# MCU_board_ATmega328p_v2_4_SN.net
KiCad netlist of a schematic drawn in EAGLE
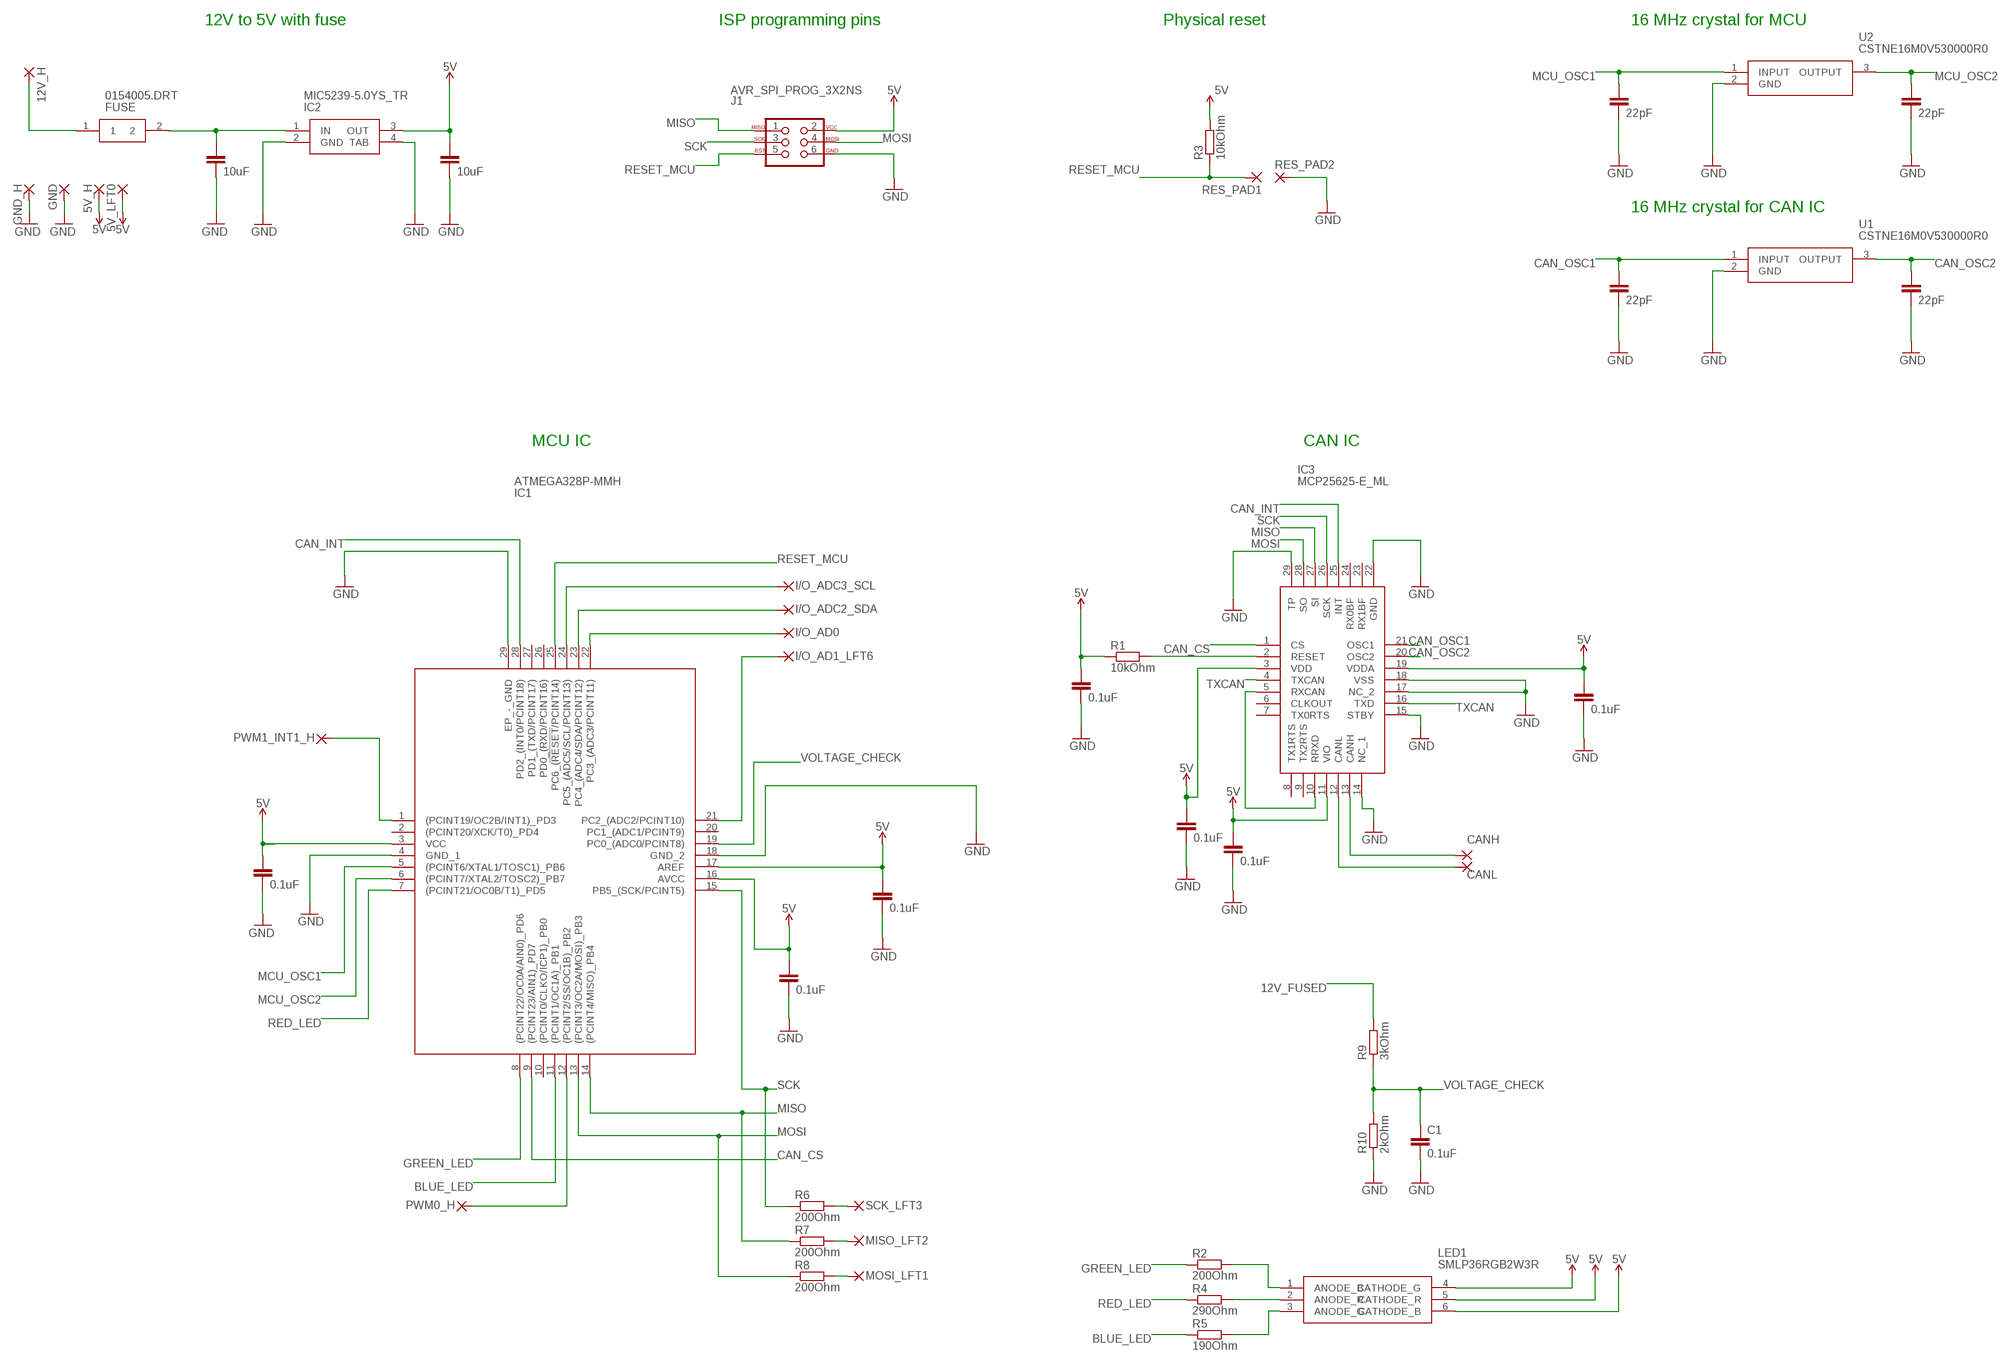
[diagram p0: schematic, sheet 1]

(export (version "E")
  (design (tool "Eeschema 10.0.6"))
  (components
    (comp (ref "5V")
      (value "5V_H")
      (footprint "eagle-import:2,15_1,0")
      (libsource (lib "eagle-import") (part "2,15/1,0"))
    )
    (comp (ref "5V1")
      (value "5V_LFT0")
      (footprint "eagle-import:2,15_1,0")
      (libsource (lib "eagle-import") (part "2,15/1,0"))
    )
    (comp (ref "12V_H")
      (value "12V")
      (footprint "eagle-import:2,15_1,0")
      (libsource (lib "eagle-import") (part "2,15/1,0"))
    )
    (comp (ref "C1")
      (value "0.1uF")
      (footprint "eagle-import:C0603")
      (libsource (lib "eagle-import") (part "CC0603"))
    )
    (comp (ref "C2")
      (value "22pF")
      (footprint "eagle-import:C0603")
      (libsource (lib "eagle-import") (part "CC0603"))
    )
    (comp (ref "C3")
      (value "22pF")
      (footprint "eagle-import:C0603")
      (libsource (lib "eagle-import") (part "CC0603"))
    )
    (comp (ref "C5")
      (value "22pF")
      (footprint "eagle-import:C0603")
      (libsource (lib "eagle-import") (part "CC0603"))
    )
    (comp (ref "C6")
      (value "0.1uF")
      (footprint "eagle-import:C0603")
      (libsource (lib "eagle-import") (part "CC0603"))
    )
    (comp (ref "C7")
      (value "0.1uF")
      (footprint "eagle-import:C0603")
      (libsource (lib "eagle-import") (part "CC0603"))
    )
    (comp (ref "C8")
      (value "0.1uF")
      (footprint "eagle-import:C0603")
      (libsource (lib "eagle-import") (part "CC0603"))
    )
    (comp (ref "C9")
      (value "22pF")
      (footprint "eagle-import:C0603")
      (libsource (lib "eagle-import") (part "CC0603"))
    )
    (comp (ref "C10")
      (value "10uF")
      (footprint "eagle-import:C0603")
      (libsource (lib "eagle-import") (part "CC0603"))
    )
    (comp (ref "C11")
      (value "10uF")
      (footprint "eagle-import:C0603")
      (libsource (lib "eagle-import") (part "CC0603"))
    )
    (comp (ref "C12")
      (value "0.1uF")
      (footprint "eagle-import:C0603")
      (libsource (lib "eagle-import") (part "CC0603"))
    )
    (comp (ref "C13")
      (value "0.1uF")
      (footprint "eagle-import:C0603")
      (libsource (lib "eagle-import") (part "CC0603"))
    )
    (comp (ref "C16")
      (value "0.1uF")
      (footprint "eagle-import:C0603")
      (libsource (lib "eagle-import") (part "CC0603"))
    )
    (comp (ref "C17")
      (value "0.1uF")
      (footprint "eagle-import:C0603")
      (libsource (lib "eagle-import") (part "CC0603"))
    )
    (comp (ref "CANH")
      (value "I/O_CANH_H")
      (footprint "eagle-import:2,15_1,0")
      (libsource (lib "eagle-import") (part "2,15/1,0"))
    )
    (comp (ref "CANL")
      (value "I/O_CANH_H")
      (footprint "eagle-import:2,15_1,0")
      (libsource (lib "eagle-import") (part "2,15/1,0"))
    )
    (comp (ref "FUSE")
      (value "0154005.DRT")
      (footprint "eagle-import:0154001.DRT")
      (fields (field (name "RS_PART_NUMBER") "2196260P"))
      (libsource (lib "eagle-import") (part "0154005.DRT"))
    )
    (comp (ref "GND")
      (value "GND_H")
      (footprint "eagle-import:2,15_1,0")
      (libsource (lib "eagle-import") (part "2,15/1,0"))
    )
    (comp (ref "GND30_H")
      (value "GND")
      (footprint "eagle-import:2,15_1,0")
      (libsource (lib "eagle-import") (part "2,15/1,0"))
    )
    (comp (ref "I/O_AD0")
      (value "I/O_AD0_LFT7")
      (footprint "eagle-import:2,15_1,0")
      (libsource (lib "eagle-import") (part "2,15/1,0"))
    )
    (comp (ref "I/O_AD1")
      (value "I/O_AD1_LFT6")
      (footprint "eagle-import:2,15_1,0")
      (libsource (lib "eagle-import") (part "2,15/1,0"))
    )
    (comp (ref "I/O_ADC2_SDA")
      (value "I/O_ADC2_SDA_LFT5")
      (footprint "eagle-import:2,15_1,0")
      (libsource (lib "eagle-import") (part "2,15/1,0"))
    )
    (comp (ref "I/O_ADC3_SCL")
      (value "I/O_ADC3_SCL_LFT4")
      (footprint "eagle-import:2,15_1,0")
      (libsource (lib "eagle-import") (part "2,15/1,0"))
    )
    (comp (ref "IC1")
      (value "ATMEGA328P-MMH")
      (footprint "eagle-import:QFN45P400X400X100-29N")
      (fields (field (name "RS_PART_NUMBER") "1310272P"))
      (libsource (lib "eagle-import") (part "ATMEGA328P-MMH"))
    )
    (comp (ref "IC2")
      (value "MIC5239-5.0YS_TR")
      (footprint "eagle-import:SOT230P700X170-4N")
      (fields
        (field (name "ARROW_PART_NUMBER") "MIC5239-5.0YS TR")
        (field (name "RS_PART_NUMBER") "7275535P")
      )
      (libsource (lib "eagle-import") (part "MIC5239-5.0YS_TR"))
    )
    (comp (ref "IC3")
      (value "MCP25625-E_ML")
      (footprint "eagle-import:QFN65P600X600X100-29N")
      (fields (field (name "ARROW_PART_NUMBER") "MCP25625-E/ML") (field (name "RS_PART_NUMBER") "1654104"))
      (libsource (lib "eagle-import") (part "MCP25625-E_ML"))
    )
    (comp (ref "J1")
      (value "AVR_SPI_PROG_3X2NS")
      (footprint "eagle-import:2X3-NS")
      (libsource (lib "eagle-import") (part "AVR_SPI_PROG_3X2NS"))
    )
    (comp (ref "LED1")
      (value "SMLP36RGB2W3R")
      (footprint "eagle-import:ROHM-1510-(0604)")
      (fields (field (name "RS_PART_NUMBER") "1246884P"))
      (libsource (lib "eagle-import") (part "SMLP36RGB2W3R"))
    )
    (comp (ref "MISO")
      (value "MISO_LFT2")
      (footprint "eagle-import:2,15_1,0")
      (libsource (lib "eagle-import") (part "2,15/1,0"))
    )
    (comp (ref "MOSI")
      (value "MOSI_LFT1")
      (footprint "eagle-import:2,15_1,0")
      (libsource (lib "eagle-import") (part "2,15/1,0"))
    )
    (comp (ref "PWM0_H")
      (value "PWM0")
      (footprint "eagle-import:2,15_1,0")
      (libsource (lib "eagle-import") (part "2,15/1,0"))
    )
    (comp (ref "PWM1_INT1_H")
      (value "PWM0_INT")
      (footprint "eagle-import:2,15_1,0")
      (libsource (lib "eagle-import") (part "2,15/1,0"))
    )
    (comp (ref "R1")
      (value "10kOhm")
      (footprint "eagle-import:R0603")
      (libsource (lib "eagle-import") (part "RR0603"))
    )
    (comp (ref "R2")
      (value "200Ohm")
      (footprint "eagle-import:R0603")
      (libsource (lib "eagle-import") (part "RR0603"))
    )
    (comp (ref "R3")
      (value "10kOhm")
      (footprint "eagle-import:R0603")
      (libsource (lib "eagle-import") (part "RR0603"))
    )
    (comp (ref "R4")
      (value "290Ohm")
      (footprint "eagle-import:R0603")
      (libsource (lib "eagle-import") (part "RR0603"))
    )
    (comp (ref "R5")
      (value "190Ohm")
      (footprint "eagle-import:R0603")
      (libsource (lib "eagle-import") (part "RR0603"))
    )
    (comp (ref "R6")
      (value "200Ohm")
      (footprint "eagle-import:R0603")
      (libsource (lib "eagle-import") (part "RR0603"))
    )
    (comp (ref "R7")
      (value "200Ohm")
      (footprint "eagle-import:R0603")
      (libsource (lib "eagle-import") (part "RR0603"))
    )
    (comp (ref "R8")
      (value "200Ohm")
      (footprint "eagle-import:R0603")
      (libsource (lib "eagle-import") (part "RR0603"))
    )
    (comp (ref "R9")
      (value "3kOhm")
      (footprint "eagle-import:R0603")
      (libsource (lib "eagle-import") (part "RR0603"))
    )
    (comp (ref "R10")
      (value "2kOhm")
      (footprint "eagle-import:R0603")
      (libsource (lib "eagle-import") (part "RR0603"))
    )
    (comp (ref "RES_PAD1")
      (value "RES_PAD")
      (footprint "eagle-import:SMD1,27-2,54")
      (libsource (lib "eagle-import") (part "SMD2"))
    )
    (comp (ref "RES_PAD2")
      (value "RES_PAD2")
      (footprint "eagle-import:SMD1,27-2,54")
      (libsource (lib "eagle-import") (part "SMD2"))
    )
    (comp (ref "SCK")
      (value "SCK_LFT3")
      (footprint "eagle-import:2,15_1,0")
      (libsource (lib "eagle-import") (part "2,15/1,0"))
    )
    (comp (ref "U1")
      (value "CSTNE16M0V530000R0")
      (footprint "eagle-import:CSTNE16M0V530000R0")
      (libsource (lib "eagle-import") (part "CSTNE16M0V530000R0"))
    )
    (comp (ref "U2")
      (value "CSTNE16M0V530000R0")
      (footprint "eagle-import:CSTNE16M0V530000R0")
      (libsource (lib "eagle-import") (part "CSTNE16M0V530000R0"))
    )
  )
  (nets
    (net (code "1") (name "/12V_FUSED") (class "Default")
      (node (ref "C10") (pin "1") (pinfunction "1_1") (pintype "passive"))
      (node (ref "FUSE") (pin "2") (pinfunction "2_2") (pintype "bidirectional"))
      (node (ref "IC2") (pin "1") (pinfunction "IN_1") (pintype "bidirectional"))
      (node (ref "R9") (pin "2") (pinfunction "2_2") (pintype "passive"))
    )
    (net (code "2") (name "/BLUE_LED") (class "Default")
      (node (ref "IC1") (pin "11") (pinfunction "(PCINT1/OC1A)_PB1_11") (pintype "bidirectional"))
      (node (ref "R5") (pin "1") (pinfunction "1_1") (pintype "passive"))
    )
    (net (code "3") (name "/CANH") (class "Default")
      (node (ref "CANH") (pin "1") (pinfunction "P_1") (pintype "passive"))
      (node (ref "IC3") (pin "13") (pinfunction "CANH_13") (pintype "bidirectional"))
    )
    (net (code "4") (name "/CANL") (class "Default")
      (node (ref "CANL") (pin "1") (pinfunction "P_1") (pintype "passive"))
      (node (ref "IC3") (pin "12") (pinfunction "CANL_12") (pintype "bidirectional"))
    )
    (net (code "5") (name "/CAN_CS") (class "Default")
      (node (ref "IC1") (pin "9") (pinfunction "(PCINT23/AIN1)_PD7_9") (pintype "bidirectional"))
      (node (ref "IC3") (pin "1") (pinfunction "CS_1") (pintype "input"))
    )
    (net (code "6") (name "/CAN_INT") (class "Default")
      (node (ref "IC1") (pin "28") (pinfunction "PD2_(INT0/PCINT18)_28") (pintype "bidirectional"))
      (node (ref "IC3") (pin "25") (pinfunction "INT_25") (pintype "input"))
    )
    (net (code "7") (name "/CAN_OSC1") (class "Default")
      (node (ref "C5") (pin "1") (pinfunction "1_1") (pintype "passive"))
      (node (ref "IC3") (pin "21") (pinfunction "OSC1_21") (pintype "bidirectional"))
      (node (ref "U1") (pin "1") (pinfunction "INPUT_1") (pintype "bidirectional"))
    )
    (net (code "8") (name "/CAN_OSC2") (class "Default")
      (node (ref "C2") (pin "1") (pinfunction "1_1") (pintype "passive"))
      (node (ref "IC3") (pin "20") (pinfunction "OSC2_20") (pintype "bidirectional"))
      (node (ref "U1") (pin "3") (pinfunction "OUTPUT_3") (pintype "bidirectional"))
    )
    (net (code "9") (name "/GREEN_LED") (class "Default")
      (node (ref "IC1") (pin "8") (pinfunction "(PCINT22/OC0A/AIN0)_PD6_8") (pintype "bidirectional"))
      (node (ref "R2") (pin "1") (pinfunction "1_1") (pintype "passive"))
    )
    (net (code "10") (name "/MCU_OSC1") (class "Default")
      (node (ref "C3") (pin "1") (pinfunction "1_1") (pintype "passive"))
      (node (ref "IC1") (pin "5") (pinfunction "(PCINT6/XTAL1/TOSC1)_PB6_5") (pintype "bidirectional"))
      (node (ref "U2") (pin "1") (pinfunction "INPUT_1") (pintype "bidirectional"))
    )
    (net (code "11") (name "/MCU_OSC2") (class "Default")
      (node (ref "C9") (pin "1") (pinfunction "1_1") (pintype "passive"))
      (node (ref "IC1") (pin "6") (pinfunction "(PCINT7/XTAL2/TOSC2)_PB7_6") (pintype "bidirectional"))
      (node (ref "U2") (pin "3") (pinfunction "OUTPUT_3") (pintype "bidirectional"))
    )
    (net (code "12") (name "/MISO") (class "Default")
      (node (ref "IC1") (pin "14") (pinfunction "(PCINT4/MISO)_PB4_14") (pintype "bidirectional"))
      (node (ref "IC3") (pin "27") (pinfunction "SI_27") (pintype "bidirectional"))
      (node (ref "J1") (pin "1") (pinfunction "1_1") (pintype "passive"))
      (node (ref "R7") (pin "1") (pinfunction "1_1") (pintype "passive"))
    )
    (net (code "13") (name "/MOSI") (class "Default")
      (node (ref "IC1") (pin "13") (pinfunction "(PCINT3/OC2A/MOSI)_PB3_13") (pintype "bidirectional"))
      (node (ref "IC3") (pin "28") (pinfunction "SO_28") (pintype "bidirectional"))
      (node (ref "J1") (pin "4") (pinfunction "4_4") (pintype "passive"))
      (node (ref "R8") (pin "1") (pinfunction "1_1") (pintype "passive"))
    )
    (net (code "14") (name "/RED_LED") (class "Default")
      (node (ref "IC1") (pin "7") (pinfunction "(PCINT21/OC0B/T1)_PD5_7") (pintype "bidirectional"))
      (node (ref "R4") (pin "1") (pinfunction "1_1") (pintype "passive"))
    )
    (net (code "15") (name "/RESET_MCU") (class "Default")
      (node (ref "IC1") (pin "25") (pinfunction "PC6_(~{RESET}/PCINT14)_25") (pintype "bidirectional"))
      (node (ref "J1") (pin "5") (pinfunction "5_5") (pintype "passive"))
      (node (ref "R3") (pin "1") (pinfunction "1_1") (pintype "passive"))
      (node (ref "RES_PAD1") (pin "1") (pinfunction "P_1") (pintype "passive"))
    )
    (net (code "16") (name "/SCK") (class "Default")
      (node (ref "IC1") (pin "15") (pinfunction "PB5_(SCK/PCINT5)_15") (pintype "bidirectional"))
      (node (ref "IC3") (pin "26") (pinfunction "SCK_26") (pintype "bidirectional"))
      (node (ref "J1") (pin "3") (pinfunction "3_3") (pintype "passive"))
      (node (ref "R6") (pin "1") (pinfunction "1_1") (pintype "passive"))
    )
    (net (code "17") (name "/TXCAN") (class "Default")
      (node (ref "IC3") (pin "16") (pinfunction "TXD_16") (pintype "bidirectional"))
      (node (ref "IC3") (pin "4") (pinfunction "TXCAN_4") (pintype "bidirectional"))
    )
    (net (code "18") (name "/VOLTAGE_CHECK") (class "Default")
      (node (ref "C1") (pin "1") (pinfunction "1_1") (pintype "passive"))
      (node (ref "IC1") (pin "19") (pinfunction "PC0_(ADC0/PCINT8)_19") (pintype "bidirectional"))
      (node (ref "R10") (pin "2") (pinfunction "2_2") (pintype "passive"))
      (node (ref "R9") (pin "1") (pinfunction "1_1") (pintype "passive"))
    )
    (net (code "19") (name "5V") (class "Default")
      (node (ref "5V") (pin "1") (pinfunction "P_1") (pintype "passive"))
      (node (ref "5V1") (pin "1") (pinfunction "P_1") (pintype "passive"))
      (node (ref "C11") (pin "1") (pinfunction "1_1") (pintype "passive"))
      (node (ref "C12") (pin "1") (pinfunction "1_1") (pintype "passive"))
      (node (ref "C13") (pin "1") (pinfunction "1_1") (pintype "passive"))
      (node (ref "C16") (pin "1") (pinfunction "1_1") (pintype "passive"))
      (node (ref "C17") (pin "1") (pinfunction "1_1") (pintype "passive"))
      (node (ref "C6") (pin "1") (pinfunction "1_1") (pintype "passive"))
      (node (ref "C7") (pin "1") (pinfunction "1_1") (pintype "passive"))
      (node (ref "C8") (pin "1") (pinfunction "1_1") (pintype "passive"))
      (node (ref "IC1") (pin "16") (pinfunction "AVCC_16") (pintype "bidirectional"))
      (node (ref "IC1") (pin "17") (pinfunction "AREF_17") (pintype "bidirectional"))
      (node (ref "IC1") (pin "3") (pinfunction "VCC_3") (pintype "bidirectional"))
      (node (ref "IC2") (pin "3") (pinfunction "OUT_3") (pintype "bidirectional"))
      (node (ref "IC3") (pin "11") (pinfunction "VIO_11") (pintype "bidirectional"))
      (node (ref "IC3") (pin "19") (pinfunction "VDDA_19") (pintype "power_in"))
      (node (ref "IC3") (pin "3") (pinfunction "VDD_3") (pintype "power_in"))
      (node (ref "J1") (pin "2") (pinfunction "2_2") (pintype "passive"))
      (node (ref "LED1") (pin "4") (pinfunction "CATHODE_G_4") (pintype "bidirectional"))
      (node (ref "LED1") (pin "5") (pinfunction "CATHODE_R_5") (pintype "bidirectional"))
      (node (ref "LED1") (pin "6") (pinfunction "CATHODE_B_6") (pintype "bidirectional"))
      (node (ref "R1") (pin "1") (pinfunction "1_1") (pintype "passive"))
      (node (ref "R3") (pin "2") (pinfunction "2_2") (pintype "passive"))
    )
    (net (code "20") (name "GND") (class "Default")
      (node (ref "C1") (pin "2") (pinfunction "2_2") (pintype "passive"))
      (node (ref "C10") (pin "2") (pinfunction "2_2") (pintype "passive"))
      (node (ref "C11") (pin "2") (pinfunction "2_2") (pintype "passive"))
      (node (ref "C12") (pin "2") (pinfunction "2_2") (pintype "passive"))
      (node (ref "C13") (pin "2") (pinfunction "2_2") (pintype "passive"))
      (node (ref "C16") (pin "2") (pinfunction "2_2") (pintype "passive"))
      (node (ref "C17") (pin "2") (pinfunction "2_2") (pintype "passive"))
      (node (ref "C2") (pin "2") (pinfunction "2_2") (pintype "passive"))
      (node (ref "C3") (pin "2") (pinfunction "2_2") (pintype "passive"))
      (node (ref "C5") (pin "2") (pinfunction "2_2") (pintype "passive"))
      (node (ref "C6") (pin "2") (pinfunction "2_2") (pintype "passive"))
      (node (ref "C7") (pin "2") (pinfunction "2_2") (pintype "passive"))
      (node (ref "C8") (pin "2") (pinfunction "2_2") (pintype "passive"))
      (node (ref "C9") (pin "2") (pinfunction "2_2") (pintype "passive"))
      (node (ref "GND") (pin "1") (pinfunction "P_1") (pintype "passive"))
      (node (ref "GND30_H") (pin "1") (pinfunction "P_1") (pintype "passive"))
      (node (ref "IC1") (pin "18") (pinfunction "GND_2_18") (pintype "bidirectional"))
      (node (ref "IC1") (pin "29") (pinfunction "EP_-_GND_29") (pintype "bidirectional"))
      (node (ref "IC1") (pin "4") (pinfunction "GND_1_4") (pintype "bidirectional"))
      (node (ref "IC2") (pin "2") (pinfunction "GND_2") (pintype "bidirectional"))
      (node (ref "IC2") (pin "4") (pinfunction "TAB_4") (pintype "bidirectional"))
      (node (ref "IC3") (pin "14") (pinfunction "NC_1_14") (pintype "bidirectional"))
      (node (ref "IC3") (pin "15") (pinfunction "STBY_15") (pintype "bidirectional"))
      (node (ref "IC3") (pin "17") (pinfunction "NC_2_17") (pintype "bidirectional"))
      (node (ref "IC3") (pin "18") (pinfunction "VSS_18") (pintype "power_in"))
      (node (ref "IC3") (pin "22") (pinfunction "GND_22") (pintype "power_in"))
      (node (ref "IC3") (pin "29") (pinfunction "TP_29") (pintype "bidirectional"))
      (node (ref "J1") (pin "6") (pinfunction "6_6") (pintype "passive"))
      (node (ref "R10") (pin "1") (pinfunction "1_1") (pintype "passive"))
      (node (ref "RES_PAD2") (pin "1") (pinfunction "P_1") (pintype "passive"))
      (node (ref "U1") (pin "2") (pinfunction "GND_2") (pintype "bidirectional"))
      (node (ref "U2") (pin "2") (pinfunction "GND_2") (pintype "bidirectional"))
    )
    (net (code "21") (name "Net-(12V_H-P)") (class "Default")
      (node (ref "12V_H") (pin "1") (pinfunction "P_1") (pintype "passive"))
      (node (ref "FUSE") (pin "1") (pinfunction "1_1") (pintype "bidirectional"))
    )
    (net (code "22") (name "Net-(I/O_AD0-P)") (class "Default")
      (node (ref "I/O_AD0") (pin "1") (pinfunction "P_1") (pintype "passive"))
      (node (ref "IC1") (pin "22") (pinfunction "PC3_(ADC3/PCINT11)_22") (pintype "bidirectional"))
    )
    (net (code "23") (name "Net-(I/O_AD1-P)") (class "Default")
      (node (ref "I/O_AD1") (pin "1") (pinfunction "P_1") (pintype "passive"))
      (node (ref "IC1") (pin "21") (pinfunction "PC2_(ADC2/PCINT10)_21") (pintype "bidirectional"))
    )
    (net (code "24") (name "Net-(I/O_ADC2_SDA-P)") (class "Default")
      (node (ref "I/O_ADC2_SDA") (pin "1") (pinfunction "P_1") (pintype "passive"))
      (node (ref "IC1") (pin "23") (pinfunction "PC4_(ADC4/SDA/PCINT12)_23") (pintype "bidirectional"))
    )
    (net (code "25") (name "Net-(I/O_ADC3_SCL-P)") (class "Default")
      (node (ref "I/O_ADC3_SCL") (pin "1") (pinfunction "P_1") (pintype "passive"))
      (node (ref "IC1") (pin "24") (pinfunction "PC5_(ADC5/SCL/PCINT13)_24") (pintype "bidirectional"))
    )
    (net (code "26") (name "Net-(IC1-(PCINT2{slash}SS{slash}OC1B)_PB2)") (class "Default")
      (node (ref "IC1") (pin "12") (pinfunction "(PCINT2/SS/OC1B)_PB2_12") (pintype "bidirectional"))
      (node (ref "PWM0_H") (pin "1") (pinfunction "P_1") (pintype "passive"))
    )
    (net (code "27") (name "Net-(IC1-(PCINT19{slash}OC2B{slash}INT1)_PD3)") (class "Default")
      (node (ref "IC1") (pin "1") (pinfunction "(PCINT19/OC2B/INT1)_PD3_1") (pintype "bidirectional"))
      (node (ref "PWM1_INT1_H") (pin "1") (pinfunction "P_1") (pintype "passive"))
    )
    (net (code "28") (name "Net-(IC3-RESET)") (class "Default")
      (node (ref "IC3") (pin "2") (pinfunction "RESET_2") (pintype "bidirectional"))
      (node (ref "R1") (pin "2") (pinfunction "2_2") (pintype "passive"))
    )
    (net (code "29") (name "Net-(IC3-RRXD)") (class "Default")
      (node (ref "IC3") (pin "10") (pinfunction "RRXD_10") (pintype "bidirectional"))
      (node (ref "IC3") (pin "5") (pinfunction "RXCAN_5") (pintype "bidirectional"))
    )
    (net (code "30") (name "Net-(LED1-ANODE_B)") (class "Default")
      (node (ref "LED1") (pin "1") (pinfunction "ANODE_B_1") (pintype "bidirectional"))
      (node (ref "R2") (pin "2") (pinfunction "2_2") (pintype "passive"))
    )
    (net (code "31") (name "Net-(LED1-ANODE_G)") (class "Default")
      (node (ref "LED1") (pin "3") (pinfunction "ANODE_G_3") (pintype "bidirectional"))
      (node (ref "R5") (pin "2") (pinfunction "2_2") (pintype "passive"))
    )
    (net (code "32") (name "Net-(LED1-ANODE_R)") (class "Default")
      (node (ref "LED1") (pin "2") (pinfunction "ANODE_R_2") (pintype "bidirectional"))
      (node (ref "R4") (pin "2") (pinfunction "2_2") (pintype "passive"))
    )
    (net (code "33") (name "Net-(MISO-P)") (class "Default")
      (node (ref "MISO") (pin "1") (pinfunction "P_1") (pintype "passive"))
      (node (ref "R7") (pin "2") (pinfunction "2_2") (pintype "passive"))
    )
    (net (code "34") (name "Net-(MOSI-P)") (class "Default")
      (node (ref "MOSI") (pin "1") (pinfunction "P_1") (pintype "passive"))
      (node (ref "R8") (pin "2") (pinfunction "2_2") (pintype "passive"))
    )
    (net (code "35") (name "Net-(SCK-P)") (class "Default")
      (node (ref "R6") (pin "2") (pinfunction "2_2") (pintype "passive"))
      (node (ref "SCK") (pin "1") (pinfunction "P_1") (pintype "passive"))
    )
    (net (code "36") (name "unconnected-(IC1-(PCINT0{slash}CLKO{slash}ICP1)_PB0-Pad10)") (class "Default")
      (node (ref "IC1") (pin "10") (pinfunction "(PCINT0/CLKO/ICP1)_PB0_10") (pintype "bidirectional"))
    )
    (net (code "37") (name "unconnected-(IC1-(PCINT20{slash}XCK{slash}T0)_PD4-Pad2)") (class "Default")
      (node (ref "IC1") (pin "2") (pinfunction "(PCINT20/XCK/T0)_PD4_2") (pintype "bidirectional"))
    )
    (net (code "38") (name "unconnected-(IC1-PC1_(ADC1{slash}PCINT9)-Pad20)") (class "Default")
      (node (ref "IC1") (pin "20") (pinfunction "PC1_(ADC1/PCINT9)_20") (pintype "bidirectional"))
    )
    (net (code "39") (name "unconnected-(IC1-PD0_(RXD{slash}PCINT16)-Pad26)") (class "Default")
      (node (ref "IC1") (pin "26") (pinfunction "PD0_(RXD/PCINT16)_26") (pintype "bidirectional"))
    )
    (net (code "40") (name "unconnected-(IC1-PD1_(TXD{slash}PCINT17)-Pad27)") (class "Default")
      (node (ref "IC1") (pin "27") (pinfunction "PD1_(TXD/PCINT17)_27") (pintype "bidirectional"))
    )
    (net (code "41") (name "unconnected-(IC3-CLKOUT-Pad6)") (class "Default")
      (node (ref "IC3") (pin "6") (pinfunction "CLKOUT_6") (pintype "output"))
    )
    (net (code "42") (name "unconnected-(IC3-RX0BF-Pad24)") (class "Default")
      (node (ref "IC3") (pin "24") (pinfunction "RX0BF_24") (pintype "bidirectional"))
    )
    (net (code "43") (name "unconnected-(IC3-RX1BF-Pad23)") (class "Default")
      (node (ref "IC3") (pin "23") (pinfunction "RX1BF_23") (pintype "bidirectional"))
    )
    (net (code "44") (name "unconnected-(IC3-TX0RTS-Pad7)") (class "Default")
      (node (ref "IC3") (pin "7") (pinfunction "TX0RTS_7") (pintype "bidirectional"))
    )
    (net (code "45") (name "unconnected-(IC3-TX1RTS-Pad8)") (class "Default")
      (node (ref "IC3") (pin "8") (pinfunction "TX1RTS_8") (pintype "bidirectional"))
    )
    (net (code "46") (name "unconnected-(IC3-TX2RTS-Pad9)") (class "Default")
      (node (ref "IC3") (pin "9") (pinfunction "TX2RTS_9") (pintype "bidirectional"))
    )
  )
)
